# EFUSE_NCP349.net
KiCad netlist of a schematic drawn in Altium Designer
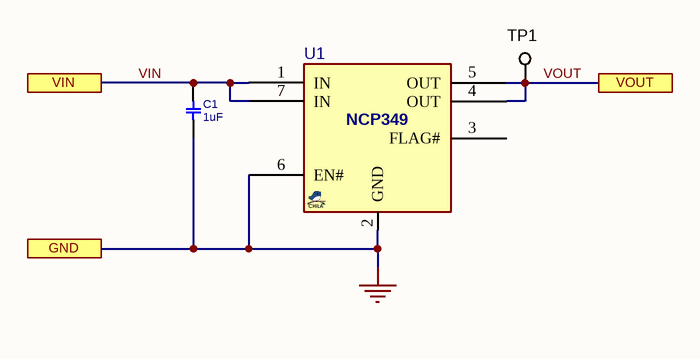
[diagram p0: EFUSE_NCP349.SchDoc]

(export (version "E")
  (design (tool "Eeschema 10.0.6"))
  (components
    (comp (ref "C1")
      (value "1uF")
      (footprint "C0402")
      (description "CAP, MLCC")
      (fields (field (name "MANF_P#") "CL05A105KO5NNND") (field (name "MANF") "Samsung"))
      (libsource (lib "passive_smd") (part "CAP_SMD_MLCC"))
    )
    (comp (ref "TP1")
      (value "TESTPOINT_SMD")
      (footprint "TPSMD_S1")
      (description "TEST POINT")
      (fields (field (name "MANF") "MANF") (field (name "MANF_P#") "MANF_P#"))
      (libsource (lib "test-tp_jumper") (part "TESTPOINT_SMD"))
    )
    (comp (ref "U1")
      (value "NCP349")
      (footprint "SON50_6T_1620")
      (description "LOAD SW, 5V eFuse, 2A, 1.2~28V, 28mOhm , DFN-6")
      (fields (field (name "MANF") "ON") (field (name "MANF_P#") "NCP349MN"))
      (libsource (lib "power_load_switch") (part "NCP349_SON6"))
    )
  )
  (nets
    (net (code "1") (name "/VIN") (class "Default")
      (node (ref "C1") (pin "2") (pinfunction "2_2") (pintype "passive"))
      (node (ref "U1") (pin "1") (pinfunction "IN_1") (pintype "passive"))
      (node (ref "U1") (pin "7") (pinfunction "IN_7") (pintype "passive"))
    )
    (net (code "2") (name "/VOUT") (class "Default")
      (node (ref "TP1") (pin "1") (pinfunction "1_1") (pintype "passive"))
      (node (ref "U1") (pin "4") (pinfunction "OUT_4") (pintype "passive"))
      (node (ref "U1") (pin "5") (pinfunction "OUT_5") (pintype "passive"))
    )
    (net (code "3") (name "GND") (class "Default")
      (node (ref "C1") (pin "1") (pinfunction "1_1") (pintype "passive"))
      (node (ref "U1") (pin "2") (pinfunction "GND_2") (pintype "passive"))
      (node (ref "U1") (pin "6") (pinfunction "EN#_6") (pintype "passive"))
    )
    (net (code "4") (name "unconnected-(U1-FLAG#-Pad3)") (class "Default")
      (node (ref "U1") (pin "3") (pinfunction "FLAG#_3") (pintype "passive"))
    )
  )
)
